# MCU.net
KiCad netlist of a schematic drawn in Altium Designer
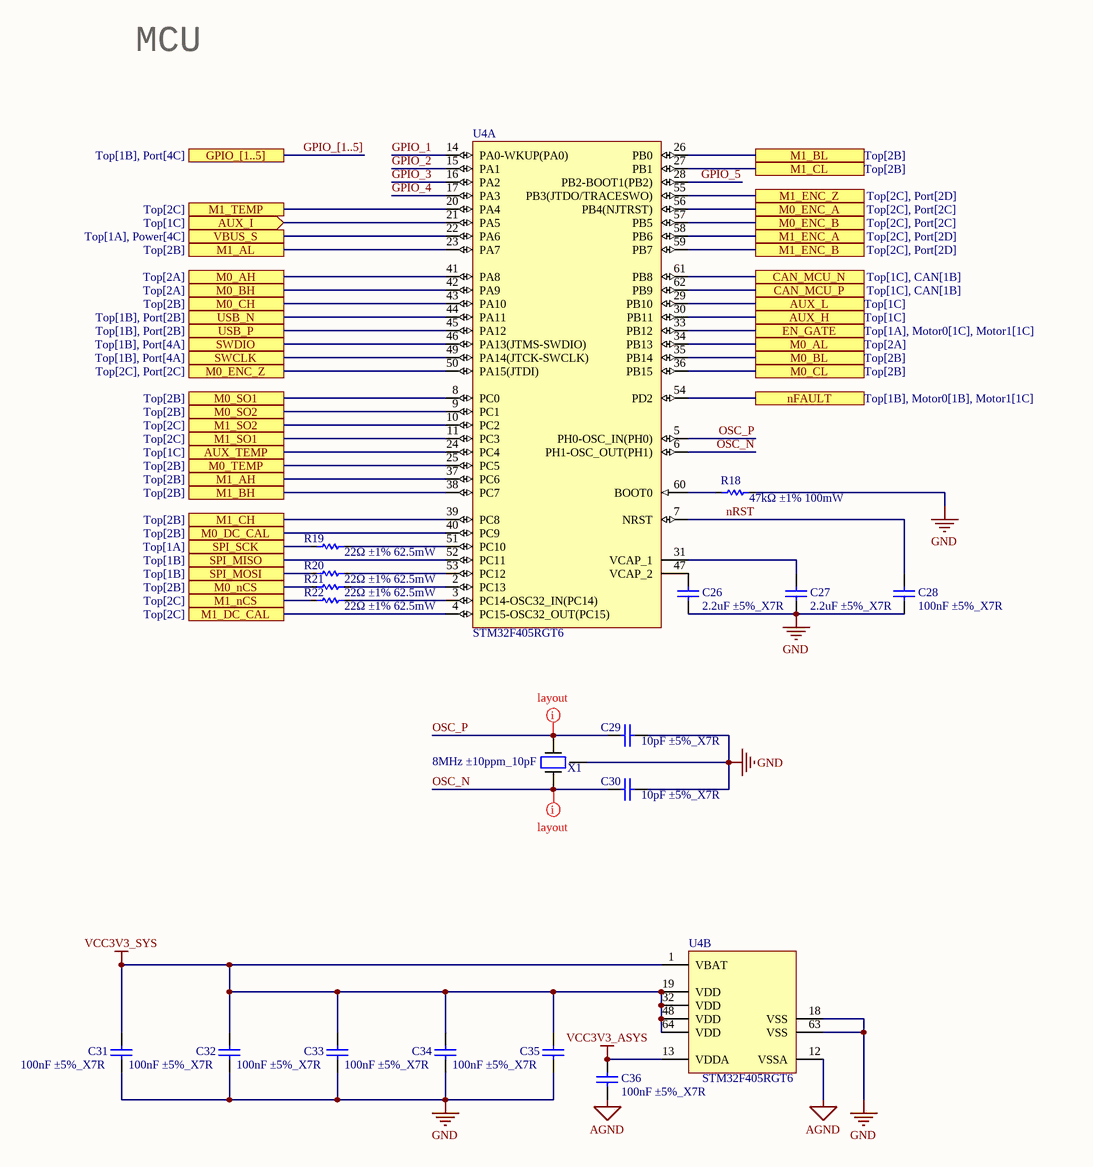
[diagram p0: MCU.SchDoc]

(export (version "E")
  (design (tool "Eeschema 10.0.6"))
  (components
    (comp (ref "C26")
      (value "2.2uF ±5%_X7R")
      (footprint "C0603")
      (description "Capacitor")
      (fields (field (name "PUBLISHER") "Altium Limited"))
      (libsource (lib "Component") (part "Cap"))
    )
    (comp (ref "C27")
      (value "2.2uF ±5%_X7R")
      (footprint "C0603")
      (description "Capacitor")
      (fields (field (name "PUBLISHER") "Altium Limited"))
      (libsource (lib "Component") (part "Cap"))
    )
    (comp (ref "C28")
      (value "100nF ±5%_X7R")
      (footprint "C0402")
      (description "Capacitor")
      (fields (field (name "PUBLISHER") "Altium Limited"))
      (libsource (lib "Component") (part "Cap"))
    )
    (comp (ref "C29")
      (value "10pF ±5%_X7R")
      (footprint "C0402")
      (description "Capacitor")
      (fields (field (name "PUBLISHER") "Altium Limited"))
      (libsource (lib "Component") (part "Cap"))
    )
    (comp (ref "C30")
      (value "10pF ±5%_X7R")
      (footprint "C0402")
      (description "Capacitor")
      (fields (field (name "PUBLISHER") "Altium Limited"))
      (libsource (lib "Component") (part "Cap"))
    )
    (comp (ref "C31")
      (value "100nF ±5%_X7R")
      (footprint "C0402")
      (description "Capacitor")
      (fields (field (name "PUBLISHER") "Altium Limited"))
      (libsource (lib "Component") (part "Cap"))
    )
    (comp (ref "C32")
      (value "100nF ±5%_X7R")
      (footprint "C0402")
      (description "Capacitor")
      (fields (field (name "PUBLISHER") "Altium Limited"))
      (libsource (lib "Component") (part "Cap"))
    )
    (comp (ref "C33")
      (value "100nF ±5%_X7R")
      (footprint "C0402")
      (description "Capacitor")
      (fields (field (name "PUBLISHER") "Altium Limited"))
      (libsource (lib "Component") (part "Cap"))
    )
    (comp (ref "C34")
      (value "100nF ±5%_X7R")
      (footprint "C0402")
      (description "Capacitor")
      (fields (field (name "PUBLISHER") "Altium Limited"))
      (libsource (lib "Component") (part "Cap"))
    )
    (comp (ref "C35")
      (value "100nF ±5%_X7R")
      (footprint "C0402")
      (description "Capacitor")
      (fields (field (name "PUBLISHER") "Altium Limited"))
      (libsource (lib "Component") (part "Cap"))
    )
    (comp (ref "C36")
      (value "100nF ±5%_X7R")
      (footprint "C0402")
      (description "Capacitor")
      (fields (field (name "PUBLISHER") "Altium Limited"))
      (libsource (lib "Component") (part "Cap"))
    )
    (comp (ref "R18")
      (value "47kΩ ±1% 100mW")
      (footprint "R0402")
      (description "Resistor")
      (fields (field (name "PUBLISHER") "Altium Limited"))
      (libsource (lib "Component") (part "Res"))
    )
    (comp (ref "R19")
      (value "22Ω ±1% 62.5mW")
      (footprint "R0402")
      (description "Resistor")
      (fields (field (name "PUBLISHER") "Altium Limited"))
      (libsource (lib "Component") (part "Res"))
    )
    (comp (ref "R20")
      (value "22Ω ±1% 62.5mW")
      (footprint "R0402")
      (description "Resistor")
      (fields (field (name "PUBLISHER") "Altium Limited"))
      (libsource (lib "Component") (part "Res"))
    )
    (comp (ref "R21")
      (value "22Ω ±1% 62.5mW")
      (footprint "R0402")
      (description "Resistor")
      (fields (field (name "PUBLISHER") "Altium Limited"))
      (libsource (lib "Component") (part "Res"))
    )
    (comp (ref "R22")
      (value "22Ω ±1% 62.5mW")
      (footprint "R0402")
      (description "Resistor")
      (fields (field (name "PUBLISHER") "Altium Limited"))
      (libsource (lib "Component") (part "Res"))
    )
    (comp (ref "U4")
      (value "STM32F405RGT6")
      (footprint "STM-LQFP64_N")
      (fields (field (name "MANUFACTURER") "STMicroelectronics"))
      (libsource (lib "STMicroelectronics STM32 F4") (part "STM32F405RGT6"))
    )
    (comp (ref "X1")
      (value "8MHz ±10ppm_10pF")
      (footprint "CRYSTAL_3225")
      (description "Crystal 8MHz ±10ppm 10pF 200 Ohm -10°C ~ 60°C Surface Mount 4-SMD, No Lead (DFN, LCC)")
      (fields
        (field (name "MANUFACTURER") "Abracon LLC")
        (field (name "MANUFACTURER PART NUMBER") "ABM3B-8.000MHZ-10-1-U-T")
      )
      (libsource (lib "Component") (part "CRYSTAL"))
    )
  )
  (nets
    (net (code "1") (name "/AUX_H") (class "Default")
      (node (ref "U4") (pin "30") (pinfunction "PB11_30") (pintype "bidirectional"))
    )
    (net (code "2") (name "/AUX_I") (class "Default")
      (node (ref "U4") (pin "21") (pinfunction "PA5_21") (pintype "bidirectional"))
    )
    (net (code "3") (name "/AUX_L") (class "Default")
      (node (ref "U4") (pin "29") (pinfunction "PB10_29") (pintype "bidirectional"))
    )
    (net (code "4") (name "/AUX_TEMP") (class "Default")
      (node (ref "U4") (pin "24") (pinfunction "PC4_24") (pintype "bidirectional"))
    )
    (net (code "5") (name "/CAN_MCU_N") (class "Default")
      (node (ref "U4") (pin "61") (pinfunction "PB8_61") (pintype "bidirectional"))
    )
    (net (code "6") (name "/CAN_MCU_P") (class "Default")
      (node (ref "U4") (pin "62") (pinfunction "PB9_62") (pintype "bidirectional"))
    )
    (net (code "7") (name "/EN_GATE") (class "Default")
      (node (ref "U4") (pin "33") (pinfunction "PB12_33") (pintype "bidirectional"))
    )
    (net (code "8") (name "/GPIO_1") (class "Default")
      (node (ref "U4") (pin "14") (pinfunction "PA0-WKUP(PA0)_14") (pintype "bidirectional"))
    )
    (net (code "9") (name "/GPIO_2") (class "Default")
      (node (ref "U4") (pin "15") (pinfunction "PA1_15") (pintype "bidirectional"))
    )
    (net (code "10") (name "/GPIO_3") (class "Default")
      (node (ref "U4") (pin "16") (pinfunction "PA2_16") (pintype "bidirectional"))
    )
    (net (code "11") (name "/GPIO_4") (class "Default")
      (node (ref "U4") (pin "17") (pinfunction "PA3_17") (pintype "bidirectional"))
    )
    (net (code "12") (name "/GPIO_5") (class "Default")
      (node (ref "U4") (pin "28") (pinfunction "PB2-BOOT1(PB2)_28") (pintype "bidirectional"))
    )
    (net (code "14") (name "/M0_AH") (class "Default")
      (node (ref "U4") (pin "41") (pinfunction "PA8_41") (pintype "bidirectional"))
    )
    (net (code "15") (name "/M0_AL") (class "Default")
      (node (ref "U4") (pin "34") (pinfunction "PB13_34") (pintype "bidirectional"))
    )
    (net (code "16") (name "/M0_BH") (class "Default")
      (node (ref "U4") (pin "42") (pinfunction "PA9_42") (pintype "bidirectional"))
    )
    (net (code "17") (name "/M0_BL") (class "Default")
      (node (ref "U4") (pin "35") (pinfunction "PB14_35") (pintype "bidirectional"))
    )
    (net (code "18") (name "/M0_CH") (class "Default")
      (node (ref "U4") (pin "43") (pinfunction "PA10_43") (pintype "bidirectional"))
    )
    (net (code "19") (name "/M0_CL") (class "Default")
      (node (ref "U4") (pin "36") (pinfunction "PB15_36") (pintype "bidirectional"))
    )
    (net (code "20") (name "/M0_DC_CAL") (class "Default")
      (node (ref "U4") (pin "40") (pinfunction "PC9_40") (pintype "bidirectional"))
    )
    (net (code "21") (name "/M0_ENC_A") (class "Default")
      (node (ref "U4") (pin "56") (pinfunction "PB4(NJTRST)_56") (pintype "bidirectional"))
    )
    (net (code "22") (name "/M0_ENC_B") (class "Default")
      (node (ref "U4") (pin "57") (pinfunction "PB5_57") (pintype "bidirectional"))
    )
    (net (code "23") (name "/M0_ENC_Z") (class "Default")
      (node (ref "U4") (pin "50") (pinfunction "PA15(JTDI)_50") (pintype "bidirectional"))
    )
    (net (code "24") (name "/M0_SO1") (class "Default")
      (node (ref "U4") (pin "8") (pinfunction "PC0_8") (pintype "bidirectional"))
    )
    (net (code "25") (name "/M0_SO2") (class "Default")
      (node (ref "U4") (pin "9") (pinfunction "PC1_9") (pintype "bidirectional"))
    )
    (net (code "26") (name "/M0_TEMP") (class "Default")
      (node (ref "U4") (pin "25") (pinfunction "PC5_25") (pintype "bidirectional"))
    )
    (net (code "27") (name "/M0_nCS") (class "Default")
      (node (ref "R21") (pin "1") (pinfunction "1_1") (pintype "passive"))
    )
    (net (code "28") (name "/M1_AH") (class "Default")
      (node (ref "U4") (pin "37") (pinfunction "PC6_37") (pintype "bidirectional"))
    )
    (net (code "29") (name "/M1_AL") (class "Default")
      (node (ref "U4") (pin "23") (pinfunction "PA7_23") (pintype "bidirectional"))
    )
    (net (code "30") (name "/M1_BH") (class "Default")
      (node (ref "U4") (pin "38") (pinfunction "PC7_38") (pintype "bidirectional"))
    )
    (net (code "31") (name "/M1_BL") (class "Default")
      (node (ref "U4") (pin "26") (pinfunction "PB0_26") (pintype "bidirectional"))
    )
    (net (code "32") (name "/M1_CH") (class "Default")
      (node (ref "U4") (pin "39") (pinfunction "PC8_39") (pintype "bidirectional"))
    )
    (net (code "33") (name "/M1_CL") (class "Default")
      (node (ref "U4") (pin "27") (pinfunction "PB1_27") (pintype "bidirectional"))
    )
    (net (code "34") (name "/M1_DC_CAL") (class "Default")
      (node (ref "U4") (pin "4") (pinfunction "PC15-OSC32_OUT(PC15)_4") (pintype "bidirectional"))
    )
    (net (code "35") (name "/M1_ENC_A") (class "Default")
      (node (ref "U4") (pin "58") (pinfunction "PB6_58") (pintype "bidirectional"))
    )
    (net (code "36") (name "/M1_ENC_B") (class "Default")
      (node (ref "U4") (pin "59") (pinfunction "PB7_59") (pintype "bidirectional"))
    )
    (net (code "37") (name "/M1_ENC_Z") (class "Default")
      (node (ref "U4") (pin "55") (pinfunction "PB3(JTDO/TRACESWO)_55") (pintype "bidirectional"))
    )
    (net (code "38") (name "/M1_SO1") (class "Default")
      (node (ref "U4") (pin "11") (pinfunction "PC3_11") (pintype "bidirectional"))
    )
    (net (code "39") (name "/M1_SO2") (class "Default")
      (node (ref "U4") (pin "10") (pinfunction "PC2_10") (pintype "bidirectional"))
    )
    (net (code "40") (name "/M1_TEMP") (class "Default")
      (node (ref "U4") (pin "20") (pinfunction "PA4_20") (pintype "bidirectional"))
    )
    (net (code "41") (name "/M1_nCS") (class "Default")
      (node (ref "R22") (pin "1") (pinfunction "1_1") (pintype "passive"))
    )
    (net (code "42") (name "/OSC_N") (class "Default")
      (node (ref "C30") (pin "1") (pinfunction "1_1") (pintype "passive"))
      (node (ref "U4") (pin "6") (pinfunction "PH1-OSC_OUT(PH1)_6") (pintype "bidirectional"))
      (node (ref "X1") (pin "1") (pintype "passive"))
    )
    (net (code "43") (name "/OSC_P") (class "Default")
      (node (ref "C29") (pin "1") (pinfunction "1_1") (pintype "passive"))
      (node (ref "U4") (pin "5") (pinfunction "PH0-OSC_IN(PH0)_5") (pintype "bidirectional"))
      (node (ref "X1") (pin "3") (pintype "passive"))
    )
    (net (code "44") (name "/SPI_MISO") (class "Default")
      (node (ref "U4") (pin "52") (pinfunction "PC11_52") (pintype "bidirectional"))
    )
    (net (code "45") (name "/SPI_MOSI") (class "Default")
      (node (ref "R20") (pin "1") (pinfunction "1_1") (pintype "passive"))
    )
    (net (code "46") (name "/SPI_SCK") (class "Default")
      (node (ref "R19") (pin "1") (pinfunction "1_1") (pintype "passive"))
    )
    (net (code "47") (name "/SWCLK") (class "Default")
      (node (ref "U4") (pin "49") (pinfunction "PA14(JTCK-SWCLK)_49") (pintype "bidirectional"))
    )
    (net (code "48") (name "/SWDIO") (class "Default")
      (node (ref "U4") (pin "46") (pinfunction "PA13(JTMS-SWDIO)_46") (pintype "bidirectional"))
    )
    (net (code "49") (name "/USB_N") (class "Default")
      (node (ref "U4") (pin "44") (pinfunction "PA11_44") (pintype "bidirectional"))
    )
    (net (code "50") (name "/USB_P") (class "Default")
      (node (ref "U4") (pin "45") (pinfunction "PA12_45") (pintype "bidirectional"))
    )
    (net (code "51") (name "/VBUS_S") (class "Default")
      (node (ref "U4") (pin "22") (pinfunction "PA6_22") (pintype "bidirectional"))
    )
    (net (code "52") (name "/nFAULT") (class "Default")
      (node (ref "U4") (pin "54") (pinfunction "PD2_54") (pintype "bidirectional"))
    )
    (net (code "53") (name "/nRST") (class "Default")
      (node (ref "C28") (pin "2") (pinfunction "2_2") (pintype "passive"))
      (node (ref "U4") (pin "7") (pinfunction "NRST_7") (pintype "bidirectional"))
    )
    (net (code "54") (name "AGND") (class "Default")
      (node (ref "C36") (pin "1") (pinfunction "1_1") (pintype "passive"))
      (node (ref "U4") (pin "12") (pinfunction "VSSA_12") (pintype "power_in"))
    )
    (net (code "55") (name "GND") (class "Default")
      (node (ref "C26") (pin "1") (pinfunction "1_1") (pintype "passive"))
      (node (ref "C27") (pin "1") (pinfunction "1_1") (pintype "passive"))
      (node (ref "C28") (pin "1") (pinfunction "1_1") (pintype "passive"))
      (node (ref "C29") (pin "2") (pinfunction "2_2") (pintype "passive"))
      (node (ref "C30") (pin "2") (pinfunction "2_2") (pintype "passive"))
      (node (ref "C31") (pin "1") (pinfunction "1_1") (pintype "passive"))
      (node (ref "C32") (pin "1") (pinfunction "1_1") (pintype "passive"))
      (node (ref "C33") (pin "1") (pinfunction "1_1") (pintype "passive"))
      (node (ref "C34") (pin "1") (pinfunction "1_1") (pintype "passive"))
      (node (ref "C35") (pin "1") (pinfunction "1_1") (pintype "passive"))
      (node (ref "R18") (pin "2") (pinfunction "2_2") (pintype "passive"))
      (node (ref "U4") (pin "18") (pinfunction "VSS_18") (pintype "power_in"))
      (node (ref "U4") (pin "63") (pinfunction "VSS_63") (pintype "power_in"))
      (node (ref "X1") (pin "G") (pintype "passive"))
    )
    (net (code "56") (name "Net-(U4A-BOOT0)") (class "Default")
      (node (ref "R18") (pin "1") (pinfunction "1_1") (pintype "passive"))
      (node (ref "U4") (pin "60") (pinfunction "BOOT0_60") (pintype "input"))
    )
    (net (code "57") (name "Net-(U4A-PC10)") (class "Default")
      (node (ref "R19") (pin "2") (pinfunction "2_2") (pintype "passive"))
      (node (ref "U4") (pin "51") (pinfunction "PC10_51") (pintype "bidirectional"))
    )
    (net (code "58") (name "Net-(U4A-PC12)") (class "Default")
      (node (ref "R20") (pin "2") (pinfunction "2_2") (pintype "passive"))
      (node (ref "U4") (pin "53") (pinfunction "PC12_53") (pintype "bidirectional"))
    )
    (net (code "59") (name "Net-(U4A-PC13)") (class "Default")
      (node (ref "R21") (pin "2") (pinfunction "2_2") (pintype "passive"))
      (node (ref "U4") (pin "2") (pinfunction "PC13_2") (pintype "bidirectional"))
    )
    (net (code "60") (name "Net-(U4A-PC14-OSC32_IN(PC14))") (class "Default")
      (node (ref "R22") (pin "2") (pinfunction "2_2") (pintype "passive"))
      (node (ref "U4") (pin "3") (pinfunction "PC14-OSC32_IN(PC14)_3") (pintype "bidirectional"))
    )
    (net (code "61") (name "Net-(U4A-VCAP_1)") (class "Default")
      (node (ref "C27") (pin "2") (pinfunction "2_2") (pintype "passive"))
      (node (ref "U4") (pin "31") (pinfunction "VCAP_1_31") (pintype "power_in"))
    )
    (net (code "62") (name "Net-(U4A-VCAP_2)") (class "Default")
      (node (ref "C26") (pin "2") (pinfunction "2_2") (pintype "passive"))
      (node (ref "U4") (pin "47") (pinfunction "VCAP_2_47") (pintype "power_in"))
    )
    (net (code "63") (name "VCC3V3_ASYS") (class "Default")
      (node (ref "C36") (pin "2") (pinfunction "2_2") (pintype "passive"))
      (node (ref "U4") (pin "13") (pinfunction "VDDA_13") (pintype "power_in"))
    )
    (net (code "64") (name "VCC3V3_SYS") (class "Default")
      (node (ref "C31") (pin "2") (pinfunction "2_2") (pintype "passive"))
      (node (ref "C32") (pin "2") (pinfunction "2_2") (pintype "passive"))
      (node (ref "C33") (pin "2") (pinfunction "2_2") (pintype "passive"))
      (node (ref "C34") (pin "2") (pinfunction "2_2") (pintype "passive"))
      (node (ref "C35") (pin "2") (pinfunction "2_2") (pintype "passive"))
      (node (ref "U4") (pin "1") (pinfunction "VBAT_1") (pintype "power_in"))
      (node (ref "U4") (pin "19") (pinfunction "VDD_19") (pintype "power_in"))
      (node (ref "U4") (pin "32") (pinfunction "VDD_32") (pintype "power_in"))
      (node (ref "U4") (pin "48") (pinfunction "VDD_48") (pintype "power_in"))
      (node (ref "U4") (pin "64") (pinfunction "VDD_64") (pintype "power_in"))
    )
  )
)
